# VSCPU_Test.net
KiCad netlist of a schematic drawn in Altium Designer
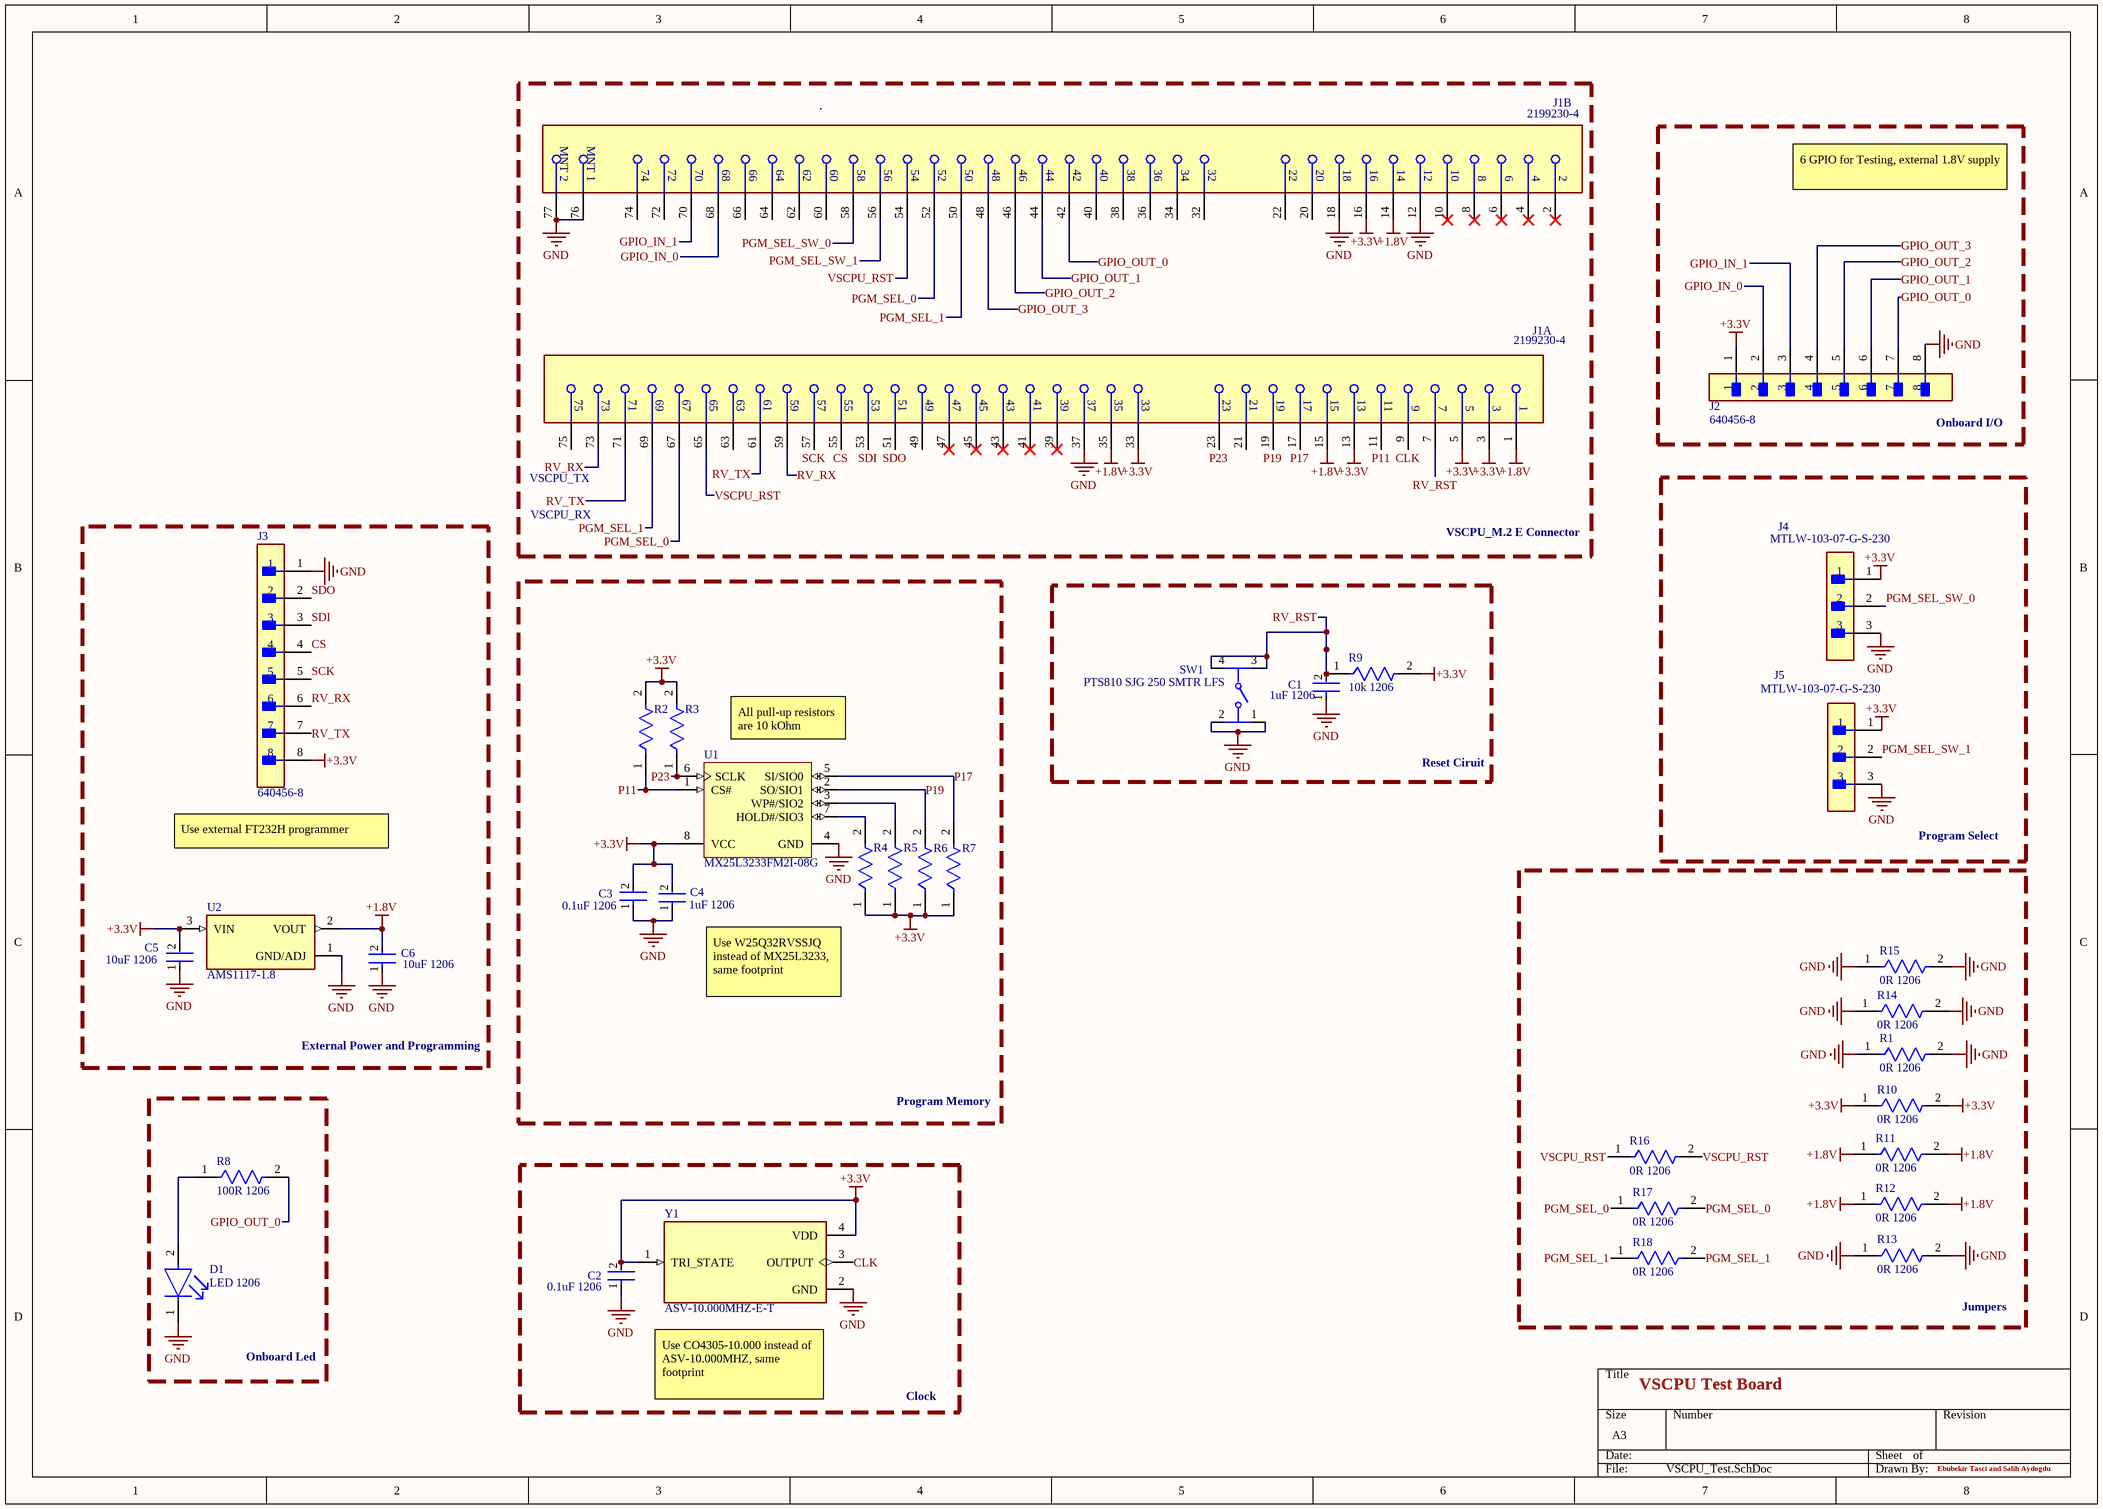
[diagram p0: VSCPU_Test.SchDoc]

(export (version "E")
  (design (tool "Eeschema 10.0.6"))
  (components
    (comp (ref "C1")
      (value "1uF 1206")
      (footprint "FP-CC1206-1_25-MFG")
      (description "CAP CER 1UF 10V X7R 1206\r\nCC1206KKX7R6BB105")
      (fields
        (field (name "MANUFACTURER") "Yageo")
        (field (name "OCTOPART") "https://octopart.com/cc1206kkx7r6bb105-yageo-21769912")
      )
      (libsource (lib "Altium Content Vault") (part "11868f565c42a9108669ba33697ecf6"))
    )
    (comp (ref "C2")
      (value "0.1uF 1206")
      (footprint "FP-C1206C-EB-MFG")
      (description "CAP CER 0.1UF 200V X7R 1206\r\nC1206C104J2RACTU")
      (fields
        (field (name "MANUFACTURER") "KEMET")
        (field (name "MANUFACTURER PART NUMBER") "C1206C104J2RACTU")
      )
      (libsource (lib "Altium Content Vault") (part "b4654b650e69147ec39a6b967a45e02"))
    )
    (comp (ref "C3")
      (value "0.1uF 1206")
      (footprint "FP-C1206C-EB-MFG")
      (description "CAP CER 0.1UF 200V X7R 1206\r\nC1206C104J2RACTU")
      (fields
        (field (name "MANUFACTURER") "KEMET")
        (field (name "MANUFACTURER PART NUMBER") "C1206C104J2RACTU")
      )
      (libsource (lib "Altium Content Vault") (part "b4654b650e69147ec39a6b967a45e02"))
    )
    (comp (ref "C4")
      (value "1uF 1206")
      (footprint "FP-CC1206-1_25-MFG")
      (description "CAP CER 1UF 10V X7R 1206\r\nCC1206KKX7R6BB105")
      (fields
        (field (name "MANUFACTURER") "Yageo")
        (field (name "OCTOPART") "https://octopart.com/cc1206kkx7r6bb105-yageo-21769912")
      )
      (libsource (lib "Altium Content Vault") (part "11868f565c42a9108669ba33697ecf6"))
    )
    (comp (ref "C5")
      (value "10uF 1206")
      (footprint "FP-CC1206-FD-MFG")
      (description "CAP CER 10UF 50V X5R 1206\r\nCC1206KKX5R9BB106")
      (fields (field (name "TOLERANCE") "10%"))
      (libsource (lib "Altium Content Vault") (part "b4654b650e69147ec39a6b967a45e02"))
    )
    (comp (ref "C6")
      (value "10uF 1206")
      (footprint "FP-CC1206-FD-MFG")
      (description "CAP CER 10UF 50V X5R 1206\r\nCC1206KKX5R9BB106")
      (fields (field (name "TOLERANCE") "10%"))
      (libsource (lib "Altium Content Vault") (part "b4654b650e69147ec39a6b967a45e02"))
    )
    (comp (ref "D1")
      (value "LED 1206")
      (footprint "FP-LTST-C150KRKT-MFG")
      (description "LED RED CLEAR 1206 SMD\r\nLTST-C150KRKT")
      (libsource (lib "Altium Content Vault") (part "8706943c75ba83719d021d2fdc84c58"))
    )
    (comp (ref "J1")
      (value "2199230-4")
      (footprint "FP-2199230-4-MFG")
      (description "CONN FEMALE 67POS 0.020 GOLD")
      (fields
        (field (name "MANUFACTURER") "TE Connectivity")
        (field (name "OCTOPART") "https://octopart.com/2199230-4-te+connectivity-46436156")
      )
      (libsource (lib "Altium Content Vault") (part "6b4bc9aaecd91677fa565b830470f16"))
    )
    (comp (ref "J2")
      (value "640456-8")
      (footprint "FP-640456-8-MFG")
      (description "CONN HEADER VERT 8POS 2.54MM")
      (libsource (lib "") (part "99ec2b232beb5d2356d4d77f6a047f0_1"))
    )
    (comp (ref "J3")
      (value "640456-8")
      (footprint "FP-640456-8-MFG")
      (description "CONN HEADER VERT 8POS 2.54MM")
      (libsource (lib "Altium Content Vault") (part "99ec2b232beb5d2356d4d77f6a047f0"))
    )
    (comp (ref "J4")
      (value "MTLW-103-07-G-S-230")
      (footprint "FP-MTLW-103-07-G-S-230-MFG")
      (description "CONN HEADER VERT 3POS 2.54MM")
      (libsource (lib "Altium Content Vault") (part "0d3f023dd272f625e17a2be33dea85f"))
    )
    (comp (ref "J5")
      (value "MTLW-103-07-G-S-230")
      (footprint "FP-MTLW-103-07-G-S-230-MFG")
      (description "CONN HEADER VERT 3POS 2.54MM")
      (libsource (lib "Altium Content Vault") (part "0d3f023dd272f625e17a2be33dea85f"))
    )
    (comp (ref "R1")
      (value "0R 1206")
      (footprint "FP-MCA1206-MFG")
      (description "Res MC Professional Thin Film 1206 0Ω Jumper 0.4W Molded Paper T/R\r\nMCA12060Z0000ZP500")
      (libsource (lib "Altium Content Vault") (part "1029c3af85768c4190bb7ad29bc67b5"))
    )
    (comp (ref "R2")
      (value "~")
      (footprint "FP-CRGCQ1206-IPC_C")
      (description "CRGCQ1206 10KΩ 0.25W 1% ±100ppm/°C 200VCRGCQ1206F10K")
      (fields (field (name "MANUFACTURER") "TE Connectivity") (field (name "TOLERANCE") "0.01"))
      (libsource (lib "Altium Content Vault") (part "1029c3af85768c4190bb7ad29bc67b5"))
    )
    (comp (ref "R3")
      (value "~")
      (footprint "FP-CRGCQ1206-IPC_C")
      (description "CRGCQ1206 10KΩ 0.25W 1% ±100ppm/°C 200VCRGCQ1206F10K")
      (fields (field (name "MANUFACTURER") "TE Connectivity") (field (name "TOLERANCE") "0.01"))
      (libsource (lib "Altium Content Vault") (part "1029c3af85768c4190bb7ad29bc67b5"))
    )
    (comp (ref "R4")
      (value "~")
      (footprint "FP-CRGCQ1206-IPC_C")
      (description "CRGCQ1206 10KΩ 0.25W 1% ±100ppm/°C 200VCRGCQ1206F10K")
      (fields (field (name "MANUFACTURER") "TE Connectivity") (field (name "TOLERANCE") "0.01"))
      (libsource (lib "Altium Content Vault") (part "1029c3af85768c4190bb7ad29bc67b5"))
    )
    (comp (ref "R5")
      (value "~")
      (footprint "FP-CRGCQ1206-IPC_C")
      (description "CRGCQ1206 10KΩ 0.25W 1% ±100ppm/°C 200VCRGCQ1206F10K")
      (fields (field (name "MANUFACTURER") "TE Connectivity") (field (name "TOLERANCE") "0.01"))
      (libsource (lib "Altium Content Vault") (part "1029c3af85768c4190bb7ad29bc67b5"))
    )
    (comp (ref "R6")
      (value "~")
      (footprint "FP-CRGCQ1206-IPC_C")
      (description "CRGCQ1206 10KΩ 0.25W 1% ±100ppm/°C 200VCRGCQ1206F10K")
      (fields (field (name "MANUFACTURER") "TE Connectivity") (field (name "TOLERANCE") "0.01"))
      (libsource (lib "Altium Content Vault") (part "1029c3af85768c4190bb7ad29bc67b5"))
    )
    (comp (ref "R7")
      (value "~")
      (footprint "FP-CRGCQ1206-IPC_C")
      (description "CRGCQ1206 10KΩ 0.25W 1% ±100ppm/°C 200VCRGCQ1206F10K")
      (fields (field (name "MANUFACTURER") "TE Connectivity") (field (name "TOLERANCE") "0.01"))
      (libsource (lib "Altium Content Vault") (part "1029c3af85768c4190bb7ad29bc67b5"))
    )
    (comp (ref "R8")
      (value "100R 1206")
      (footprint "FP-MCA1206-IPC_B")
      (fields (field (name "TOLERANCE") "0.5%"))
      (libsource (lib "Altium Content Vault") (part "1029c3af85768c4190bb7ad29bc67b5"))
    )
    (comp (ref "R9")
      (value "10k 1206")
      (footprint "FP-CRGCQ1206-IPC_C")
      (description "CRGCQ1206 10KΩ 0.25W 1% ±100ppm/°C 200VCRGCQ1206F10K")
      (fields (field (name "MANUFACTURER") "TE Connectivity") (field (name "TOLERANCE") "0.01"))
      (libsource (lib "Altium Content Vault") (part "1029c3af85768c4190bb7ad29bc67b5"))
    )
    (comp (ref "R10")
      (value "0R 1206")
      (footprint "FP-MCA1206-MFG")
      (description "Res MC Professional Thin Film 1206 0Ω Jumper 0.4W Molded Paper T/R\r\nMCA12060Z0000ZP500")
      (libsource (lib "Altium Content Vault") (part "1029c3af85768c4190bb7ad29bc67b5"))
    )
    (comp (ref "R11")
      (value "0R 1206")
      (footprint "FP-MCA1206-MFG")
      (description "Res MC Professional Thin Film 1206 0Ω Jumper 0.4W Molded Paper T/R\r\nMCA12060Z0000ZP500")
      (libsource (lib "Altium Content Vault") (part "1029c3af85768c4190bb7ad29bc67b5"))
    )
    (comp (ref "R12")
      (value "0R 1206")
      (footprint "FP-MCA1206-MFG")
      (description "Res MC Professional Thin Film 1206 0Ω Jumper 0.4W Molded Paper T/R\r\nMCA12060Z0000ZP500")
      (libsource (lib "Altium Content Vault") (part "1029c3af85768c4190bb7ad29bc67b5"))
    )
    (comp (ref "R13")
      (value "0R 1206")
      (footprint "FP-MCA1206-MFG")
      (description "Res MC Professional Thin Film 1206 0Ω Jumper 0.4W Molded Paper T/R\r\nMCA12060Z0000ZP500")
      (libsource (lib "Altium Content Vault") (part "1029c3af85768c4190bb7ad29bc67b5"))
    )
    (comp (ref "R14")
      (value "0R 1206")
      (footprint "FP-MCA1206-MFG")
      (description "Res MC Professional Thin Film 1206 0Ω Jumper 0.4W Molded Paper T/R\r\nMCA12060Z0000ZP500")
      (libsource (lib "Altium Content Vault") (part "1029c3af85768c4190bb7ad29bc67b5"))
    )
    (comp (ref "R15")
      (value "0R 1206")
      (footprint "FP-MCA1206-MFG")
      (description "Res MC Professional Thin Film 1206 0Ω Jumper 0.4W Molded Paper T/R\r\nMCA12060Z0000ZP500")
      (libsource (lib "Altium Content Vault") (part "1029c3af85768c4190bb7ad29bc67b5"))
    )
    (comp (ref "R16")
      (value "0R 1206")
      (footprint "FP-MCA1206-MFG")
      (description "Res MC Professional Thin Film 1206 0Ω Jumper 0.4W Molded Paper T/R\r\nMCA12060Z0000ZP500")
      (libsource (lib "Altium Content Vault") (part "1029c3af85768c4190bb7ad29bc67b5"))
    )
    (comp (ref "R17")
      (value "0R 1206")
      (footprint "FP-MCA1206-MFG")
      (description "Res MC Professional Thin Film 1206 0Ω Jumper 0.4W Molded Paper T/R\r\nMCA12060Z0000ZP500")
      (libsource (lib "Altium Content Vault") (part "1029c3af85768c4190bb7ad29bc67b5"))
    )
    (comp (ref "R18")
      (value "0R 1206")
      (footprint "FP-MCA1206-MFG")
      (description "Res MC Professional Thin Film 1206 0Ω Jumper 0.4W Molded Paper T/R\r\nMCA12060Z0000ZP500")
      (libsource (lib "Altium Content Vault") (part "1029c3af85768c4190bb7ad29bc67b5"))
    )
    (comp (ref "SW1")
      (value "PTS810 SJG 250 SMTR LFS")
      (footprint "FP-PTS810_SJG_250_SMTR_LF-MFG")
      (description "SWITCH TACTILE SPST-NO 0.05A 16V")
      (fields
        (field (name "MANUFACTURER") "C&K Components")
        (field (name "OCTOPART") "https://octopart.com/pts810sjg250smtrlfs-c%26k+components-29380277")
      )
      (libsource (lib "Altium Content Vault") (part "1adf0dd01260c80cf25a44bfd6b99ba"))
    )
    (comp (ref "U1")
      (value "MX25L3233FM2I-08G")
      (footprint "MXIC-SOP-8_N")
      (fields (field (name "MANUFACTURER") "Macronix"))
      (libsource (lib "Altium Content Vault") (part "MXIC-MX25L3233FM2I-08G-SOP-8"))
    )
    (comp (ref "U2")
      (value "AMS1117-1.8")
      (footprint "SOT229P700X180-4N")
      (libsource (lib "Ebubekir Taşcı") (part "AMS1117-1.8"))
    )
    (comp (ref "Y1")
      (value "ASV-10.000MHZ-E-T")
      (footprint "XTAL_ASV-10.000MHZ-E-T")
      (libsource (lib "Ebubekir Taşcı") (part "ASV-10.000MHZ-E-T"))
    )
  )
  (nets
    (net (code "1") (name "+1.8V") (class "Default")
      (node (ref "C6") (pin "2") (pinfunction "2_2") (pintype "passive"))
      (node (ref "J1") (pin "1") (pinfunction "1_1") (pintype "passive"))
      (node (ref "J1") (pin "14") (pinfunction "14_14") (pintype "passive"))
      (node (ref "J1") (pin "15") (pinfunction "15_15") (pintype "passive"))
      (node (ref "J1") (pin "35") (pinfunction "35_35") (pintype "passive"))
      (node (ref "R11") (pin "1") (pinfunction "1_1") (pintype "passive"))
      (node (ref "R11") (pin "2") (pinfunction "2_2") (pintype "passive"))
      (node (ref "R12") (pin "1") (pinfunction "1_1") (pintype "passive"))
      (node (ref "R12") (pin "2") (pinfunction "2_2") (pintype "passive"))
      (node (ref "U2") (pin "2") (pinfunction "VOUT_2") (pintype "output"))
    )
    (net (code "2") (name "+3.3V") (class "Default")
      (node (ref "C2") (pin "2") (pinfunction "2_2") (pintype "passive"))
      (node (ref "C3") (pin "2") (pinfunction "2_2") (pintype "passive"))
      (node (ref "C4") (pin "2") (pinfunction "2_2") (pintype "passive"))
      (node (ref "C5") (pin "2") (pinfunction "2_2") (pintype "passive"))
      (node (ref "J1") (pin "13") (pinfunction "13_13") (pintype "passive"))
      (node (ref "J1") (pin "16") (pinfunction "16_16") (pintype "passive"))
      (node (ref "J1") (pin "3") (pinfunction "3_3") (pintype "passive"))
      (node (ref "J1") (pin "33") (pinfunction "33_33") (pintype "passive"))
      (node (ref "J1") (pin "5") (pinfunction "5_5") (pintype "passive"))
      (node (ref "J2") (pin "1") (pinfunction "1_1") (pintype "passive"))
      (node (ref "J3") (pin "8") (pinfunction "8_8") (pintype "passive"))
      (node (ref "J4") (pin "1") (pinfunction "1_1") (pintype "passive"))
      (node (ref "J5") (pin "1") (pinfunction "1_1") (pintype "passive"))
      (node (ref "R10") (pin "1") (pinfunction "1_1") (pintype "passive"))
      (node (ref "R10") (pin "2") (pinfunction "2_2") (pintype "passive"))
      (node (ref "R2") (pin "2") (pinfunction "2_2") (pintype "passive"))
      (node (ref "R3") (pin "2") (pinfunction "2_2") (pintype "passive"))
      (node (ref "R4") (pin "1") (pinfunction "1_1") (pintype "passive"))
      (node (ref "R5") (pin "1") (pinfunction "1_1") (pintype "passive"))
      (node (ref "R6") (pin "1") (pinfunction "1_1") (pintype "passive"))
      (node (ref "R7") (pin "1") (pinfunction "1_1") (pintype "passive"))
      (node (ref "R9") (pin "2") (pinfunction "2_2") (pintype "passive"))
      (node (ref "U1") (pin "8") (pinfunction "VCC_8") (pintype "power_in"))
      (node (ref "U2") (pin "3") (pinfunction "VIN_3") (pintype "input"))
      (node (ref "Y1") (pin "1") (pinfunction "TRI_STATE_1") (pintype "input"))
      (node (ref "Y1") (pin "4") (pinfunction "VDD_4") (pintype "power_in"))
    )
    (net (code "3") (name "/CLK") (class "Default")
      (node (ref "J1") (pin "9") (pinfunction "9_9") (pintype "passive"))
      (node (ref "Y1") (pin "3") (pinfunction "OUTPUT_3") (pintype "output"))
    )
    (net (code "4") (name "/CS") (class "Default")
      (node (ref "J1") (pin "55") (pinfunction "55_55") (pintype "passive"))
      (node (ref "J3") (pin "4") (pinfunction "4_4") (pintype "passive"))
    )
    (net (code "5") (name "/GPIO_IN_0") (class "Default")
      (node (ref "J1") (pin "68") (pinfunction "68_68") (pintype "passive"))
      (node (ref "J2") (pin "2") (pinfunction "2_2") (pintype "passive"))
    )
    (net (code "6") (name "/GPIO_IN_1") (class "Default")
      (node (ref "J1") (pin "70") (pinfunction "70_70") (pintype "passive"))
      (node (ref "J2") (pin "3") (pinfunction "3_3") (pintype "passive"))
    )
    (net (code "7") (name "/GPIO_OUT_0") (class "Default")
      (node (ref "J1") (pin "42") (pinfunction "42_42") (pintype "passive"))
      (node (ref "J2") (pin "7") (pinfunction "7_7") (pintype "passive"))
      (node (ref "R8") (pin "2") (pinfunction "2_2") (pintype "passive"))
    )
    (net (code "8") (name "/GPIO_OUT_1") (class "Default")
      (node (ref "J1") (pin "44") (pinfunction "44_44") (pintype "passive"))
      (node (ref "J2") (pin "6") (pinfunction "6_6") (pintype "passive"))
    )
    (net (code "9") (name "/GPIO_OUT_2") (class "Default")
      (node (ref "J1") (pin "46") (pinfunction "46_46") (pintype "passive"))
      (node (ref "J2") (pin "5") (pinfunction "5_5") (pintype "passive"))
    )
    (net (code "10") (name "/GPIO_OUT_3") (class "Default")
      (node (ref "J1") (pin "48") (pinfunction "48_48") (pintype "passive"))
      (node (ref "J2") (pin "4") (pinfunction "4_4") (pintype "passive"))
    )
    (net (code "11") (name "/P11") (class "Default")
      (node (ref "J1") (pin "11") (pinfunction "11_11") (pintype "passive"))
      (node (ref "R2") (pin "1") (pinfunction "1_1") (pintype "passive"))
      (node (ref "U1") (pin "1") (pinfunction "CS#_1") (pintype "input"))
    )
    (net (code "12") (name "/P17") (class "Default")
      (node (ref "J1") (pin "17") (pinfunction "17_17") (pintype "passive"))
      (node (ref "R7") (pin "2") (pinfunction "2_2") (pintype "passive"))
      (node (ref "U1") (pin "5") (pinfunction "SI/SIO0_5") (pintype "bidirectional"))
    )
    (net (code "13") (name "/P19") (class "Default")
      (node (ref "J1") (pin "19") (pinfunction "19_19") (pintype "passive"))
      (node (ref "R6") (pin "2") (pinfunction "2_2") (pintype "passive"))
      (node (ref "U1") (pin "2") (pinfunction "SO/SIO1_2") (pintype "bidirectional"))
    )
    (net (code "14") (name "/P23") (class "Default")
      (node (ref "J1") (pin "23") (pinfunction "23_23") (pintype "passive"))
      (node (ref "R3") (pin "1") (pinfunction "1_1") (pintype "passive"))
      (node (ref "U1") (pin "6") (pinfunction "SCLK_6") (pintype "input"))
    )
    (net (code "15") (name "/PGM_SEL_0") (class "Default")
      (node (ref "J1") (pin "52") (pinfunction "52_52") (pintype "passive"))
      (node (ref "J1") (pin "67") (pinfunction "67_67") (pintype "passive"))
      (node (ref "R17") (pin "1") (pinfunction "1_1") (pintype "passive"))
      (node (ref "R17") (pin "2") (pinfunction "2_2") (pintype "passive"))
    )
    (net (code "16") (name "/PGM_SEL_1") (class "Default")
      (node (ref "J1") (pin "50") (pinfunction "50_50") (pintype "passive"))
      (node (ref "J1") (pin "69") (pinfunction "69_69") (pintype "passive"))
      (node (ref "R18") (pin "1") (pinfunction "1_1") (pintype "passive"))
      (node (ref "R18") (pin "2") (pinfunction "2_2") (pintype "passive"))
    )
    (net (code "17") (name "/PGM_SEL_SW_0") (class "Default")
      (node (ref "J1") (pin "58") (pinfunction "58_58") (pintype "passive"))
      (node (ref "J4") (pin "2") (pinfunction "2_2") (pintype "passive"))
    )
    (net (code "18") (name "/PGM_SEL_SW_1") (class "Default")
      (node (ref "J1") (pin "56") (pinfunction "56_56") (pintype "passive"))
      (node (ref "J5") (pin "2") (pinfunction "2_2") (pintype "passive"))
    )
    (net (code "19") (name "/RV_RST") (class "Default")
      (node (ref "C1") (pin "2") (pinfunction "2_2") (pintype "passive"))
      (node (ref "J1") (pin "7") (pinfunction "7_7") (pintype "passive"))
      (node (ref "R9") (pin "1") (pinfunction "1_1") (pintype "passive"))
      (node (ref "SW1") (pin "3") (pinfunction "3_3") (pintype "passive"))
      (node (ref "SW1") (pin "4") (pinfunction "4_4") (pintype "passive"))
    )
    (net (code "20") (name "/RV_RX") (class "Default")
      (node (ref "J1") (pin "59") (pinfunction "59_59") (pintype "passive"))
      (node (ref "J1") (pin "73") (pinfunction "73_73") (pintype "passive"))
      (node (ref "J3") (pin "6") (pinfunction "6_6") (pintype "passive"))
    )
    (net (code "21") (name "/RV_TX") (class "Default")
      (node (ref "J1") (pin "61") (pinfunction "61_61") (pintype "passive"))
      (node (ref "J1") (pin "71") (pinfunction "71_71") (pintype "passive"))
      (node (ref "J3") (pin "7") (pinfunction "7_7") (pintype "passive"))
    )
    (net (code "22") (name "/SCK") (class "Default")
      (node (ref "J1") (pin "57") (pinfunction "57_57") (pintype "passive"))
      (node (ref "J3") (pin "5") (pinfunction "5_5") (pintype "passive"))
    )
    (net (code "23") (name "/SDI") (class "Default")
      (node (ref "J1") (pin "53") (pinfunction "53_53") (pintype "passive"))
      (node (ref "J3") (pin "3") (pinfunction "3_3") (pintype "passive"))
    )
    (net (code "24") (name "/SDO") (class "Default")
      (node (ref "J1") (pin "51") (pinfunction "51_51") (pintype "passive"))
      (node (ref "J3") (pin "2") (pinfunction "2_2") (pintype "passive"))
    )
    (net (code "25") (name "/VSCPU_RST") (class "Default")
      (node (ref "J1") (pin "54") (pinfunction "54_54") (pintype "passive"))
      (node (ref "J1") (pin "65") (pinfunction "65_65") (pintype "passive"))
      (node (ref "R16") (pin "1") (pinfunction "1_1") (pintype "passive"))
      (node (ref "R16") (pin "2") (pinfunction "2_2") (pintype "passive"))
    )
    (net (code "26") (name "GND") (class "Default")
      (node (ref "C1") (pin "1") (pinfunction "1_1") (pintype "passive"))
      (node (ref "C2") (pin "1") (pinfunction "1_1") (pintype "passive"))
      (node (ref "C3") (pin "1") (pinfunction "1_1") (pintype "passive"))
      (node (ref "C4") (pin "1") (pinfunction "1_1") (pintype "passive"))
      (node (ref "C5") (pin "1") (pinfunction "1_1") (pintype "passive"))
      (node (ref "C6") (pin "1") (pinfunction "1_1") (pintype "passive"))
      (node (ref "D1") (pin "1") (pinfunction "C_1") (pintype "passive"))
      (node (ref "J1") (pin "12") (pinfunction "12_12") (pintype "passive"))
      (node (ref "J1") (pin "18") (pinfunction "18_18") (pintype "passive"))
      (node (ref "J1") (pin "37") (pinfunction "37_37") (pintype "passive"))
      (node (ref "J1") (pin "76") (pinfunction "MNT_1_76") (pintype "passive"))
      (node (ref "J1") (pin "77") (pinfunction "MNT_2_77") (pintype "passive"))
      (node (ref "J2") (pin "8") (pinfunction "8_8") (pintype "passive"))
      (node (ref "J3") (pin "1") (pinfunction "1_1") (pintype "passive"))
      (node (ref "J4") (pin "3") (pinfunction "3_3") (pintype "passive"))
      (node (ref "J5") (pin "3") (pinfunction "3_3") (pintype "passive"))
      (node (ref "R1") (pin "1") (pinfunction "1_1") (pintype "passive"))
      (node (ref "R1") (pin "2") (pinfunction "2_2") (pintype "passive"))
      (node (ref "R13") (pin "1") (pinfunction "1_1") (pintype "passive"))
      (node (ref "R13") (pin "2") (pinfunction "2_2") (pintype "passive"))
      (node (ref "R14") (pin "1") (pinfunction "1_1") (pintype "passive"))
      (node (ref "R14") (pin "2") (pinfunction "2_2") (pintype "passive"))
      (node (ref "R15") (pin "1") (pinfunction "1_1") (pintype "passive"))
      (node (ref "R15") (pin "2") (pinfunction "2_2") (pintype "passive"))
      (node (ref "SW1") (pin "1") (pinfunction "1_1") (pintype "passive"))
      (node (ref "SW1") (pin "2") (pinfunction "2_2") (pintype "passive"))
      (node (ref "U1") (pin "4") (pinfunction "GND_4") (pintype "power_in"))
      (node (ref "U2") (pin "1") (pinfunction "GND/ADJ_1") (pintype "power_in"))
      (node (ref "Y1") (pin "2") (pinfunction "GND_2") (pintype "power_in"))
    )
    (net (code "27") (name "Net-(D1-A)") (class "Default")
      (node (ref "D1") (pin "2") (pinfunction "A_2") (pintype "passive"))
      (node (ref "R8") (pin "1") (pinfunction "1_1") (pintype "passive"))
    )
    (net (code "28") (name "Net-(U1-HOLD#{slash}SIO3)") (class "Default")
      (node (ref "R4") (pin "2") (pinfunction "2_2") (pintype "passive"))
      (node (ref "U1") (pin "7") (pinfunction "HOLD#/SIO3_7") (pintype "bidirectional"))
    )
    (net (code "29") (name "Net-(U1-WP#{slash}SIO2)") (class "Default")
      (node (ref "R5") (pin "2") (pinfunction "2_2") (pintype "passive"))
      (node (ref "U1") (pin "3") (pinfunction "WP#/SIO2_3") (pintype "bidirectional"))
    )
    (net (code "30") (name "unconnected-(J1-Pad2)") (class "Default")
      (node (ref "J1") (pin "2") (pinfunction "2_2") (pintype "passive+no_connect"))
    )
    (net (code "31") (name "unconnected-(J1-Pad4)") (class "Default")
      (node (ref "J1") (pin "4") (pinfunction "4_4") (pintype "passive+no_connect"))
    )
    (net (code "32") (name "unconnected-(J1-Pad6)") (class "Default")
      (node (ref "J1") (pin "6") (pinfunction "6_6") (pintype "passive+no_connect"))
    )
    (net (code "33") (name "unconnected-(J1-Pad8)") (class "Default")
      (node (ref "J1") (pin "8") (pinfunction "8_8") (pintype "passive+no_connect"))
    )
    (net (code "34") (name "unconnected-(J1-Pad10)") (class "Default")
      (node (ref "J1") (pin "10") (pinfunction "10_10") (pintype "passive+no_connect"))
    )
    (net (code "35") (name "unconnected-(J1-Pad20)") (class "Default")
      (node (ref "J1") (pin "20") (pinfunction "20_20") (pintype "passive"))
    )
    (net (code "36") (name "unconnected-(J1-Pad21)") (class "Default")
      (node (ref "J1") (pin "21") (pinfunction "21_21") (pintype "passive"))
    )
    (net (code "37") (name "unconnected-(J1-Pad22)") (class "Default")
      (node (ref "J1") (pin "22") (pinfunction "22_22") (pintype "passive"))
    )
    (net (code "38") (name "unconnected-(J1-Pad32)") (class "Default")
      (node (ref "J1") (pin "32") (pinfunction "32_32") (pintype "passive"))
    )
    (net (code "39") (name "unconnected-(J1-Pad34)") (class "Default")
      (node (ref "J1") (pin "34") (pinfunction "34_34") (pintype "passive"))
    )
    (net (code "40") (name "unconnected-(J1-Pad36)") (class "Default")
      (node (ref "J1") (pin "36") (pinfunction "36_36") (pintype "passive"))
    )
    (net (code "41") (name "unconnected-(J1-Pad38)") (class "Default")
      (node (ref "J1") (pin "38") (pinfunction "38_38") (pintype "passive"))
    )
    (net (code "42") (name "unconnected-(J1-Pad39)") (class "Default")
      (node (ref "J1") (pin "39") (pinfunction "39_39") (pintype "passive+no_connect"))
    )
    (net (code "43") (name "unconnected-(J1-Pad40)") (class "Default")
      (node (ref "J1") (pin "40") (pinfunction "40_40") (pintype "passive"))
    )
    (net (code "44") (name "unconnected-(J1-Pad41)") (class "Default")
      (node (ref "J1") (pin "41") (pinfunction "41_41") (pintype "passive+no_connect"))
    )
    (net (code "45") (name "unconnected-(J1-Pad43)") (class "Default")
      (node (ref "J1") (pin "43") (pinfunction "43_43") (pintype "passive+no_connect"))
    )
    (net (code "46") (name "unconnected-(J1-Pad45)") (class "Default")
      (node (ref "J1") (pin "45") (pinfunction "45_45") (pintype "passive+no_connect"))
    )
    (net (code "47") (name "unconnected-(J1-Pad47)") (class "Default")
      (node (ref "J1") (pin "47") (pinfunction "47_47") (pintype "passive+no_connect"))
    )
    (net (code "48") (name "unconnected-(J1-Pad49)") (class "Default")
      (node (ref "J1") (pin "49") (pinfunction "49_49") (pintype "passive"))
    )
    (net (code "49") (name "unconnected-(J1-Pad60)") (class "Default")
      (node (ref "J1") (pin "60") (pinfunction "60_60") (pintype "passive"))
    )
    (net (code "50") (name "unconnected-(J1-Pad62)") (class "Default")
      (node (ref "J1") (pin "62") (pinfunction "62_62") (pintype "passive"))
    )
    (net (code "51") (name "unconnected-(J1-Pad63)") (class "Default")
      (node (ref "J1") (pin "63") (pinfunction "63_63") (pintype "passive"))
    )
    (net (code "52") (name "unconnected-(J1-Pad64)") (class "Default")
      (node (ref "J1") (pin "64") (pinfunction "64_64") (pintype "passive"))
    )
    (net (code "53") (name "unconnected-(J1-Pad66)") (class "Default")
      (node (ref "J1") (pin "66") (pinfunction "66_66") (pintype "passive"))
    )
    (net (code "54") (name "unconnected-(J1-Pad72)") (class "Default")
      (node (ref "J1") (pin "72") (pinfunction "72_72") (pintype "passive"))
    )
    (net (code "55") (name "unconnected-(J1-Pad74)") (class "Default")
      (node (ref "J1") (pin "74") (pinfunction "74_74") (pintype "passive"))
    )
    (net (code "56") (name "unconnected-(J1-Pad75)") (class "Default")
      (node (ref "J1") (pin "75") (pinfunction "75_75") (pintype "passive"))
    )
  )
)
